# main_board.net
KiCad netlist of a schematic drawn in EAGLE
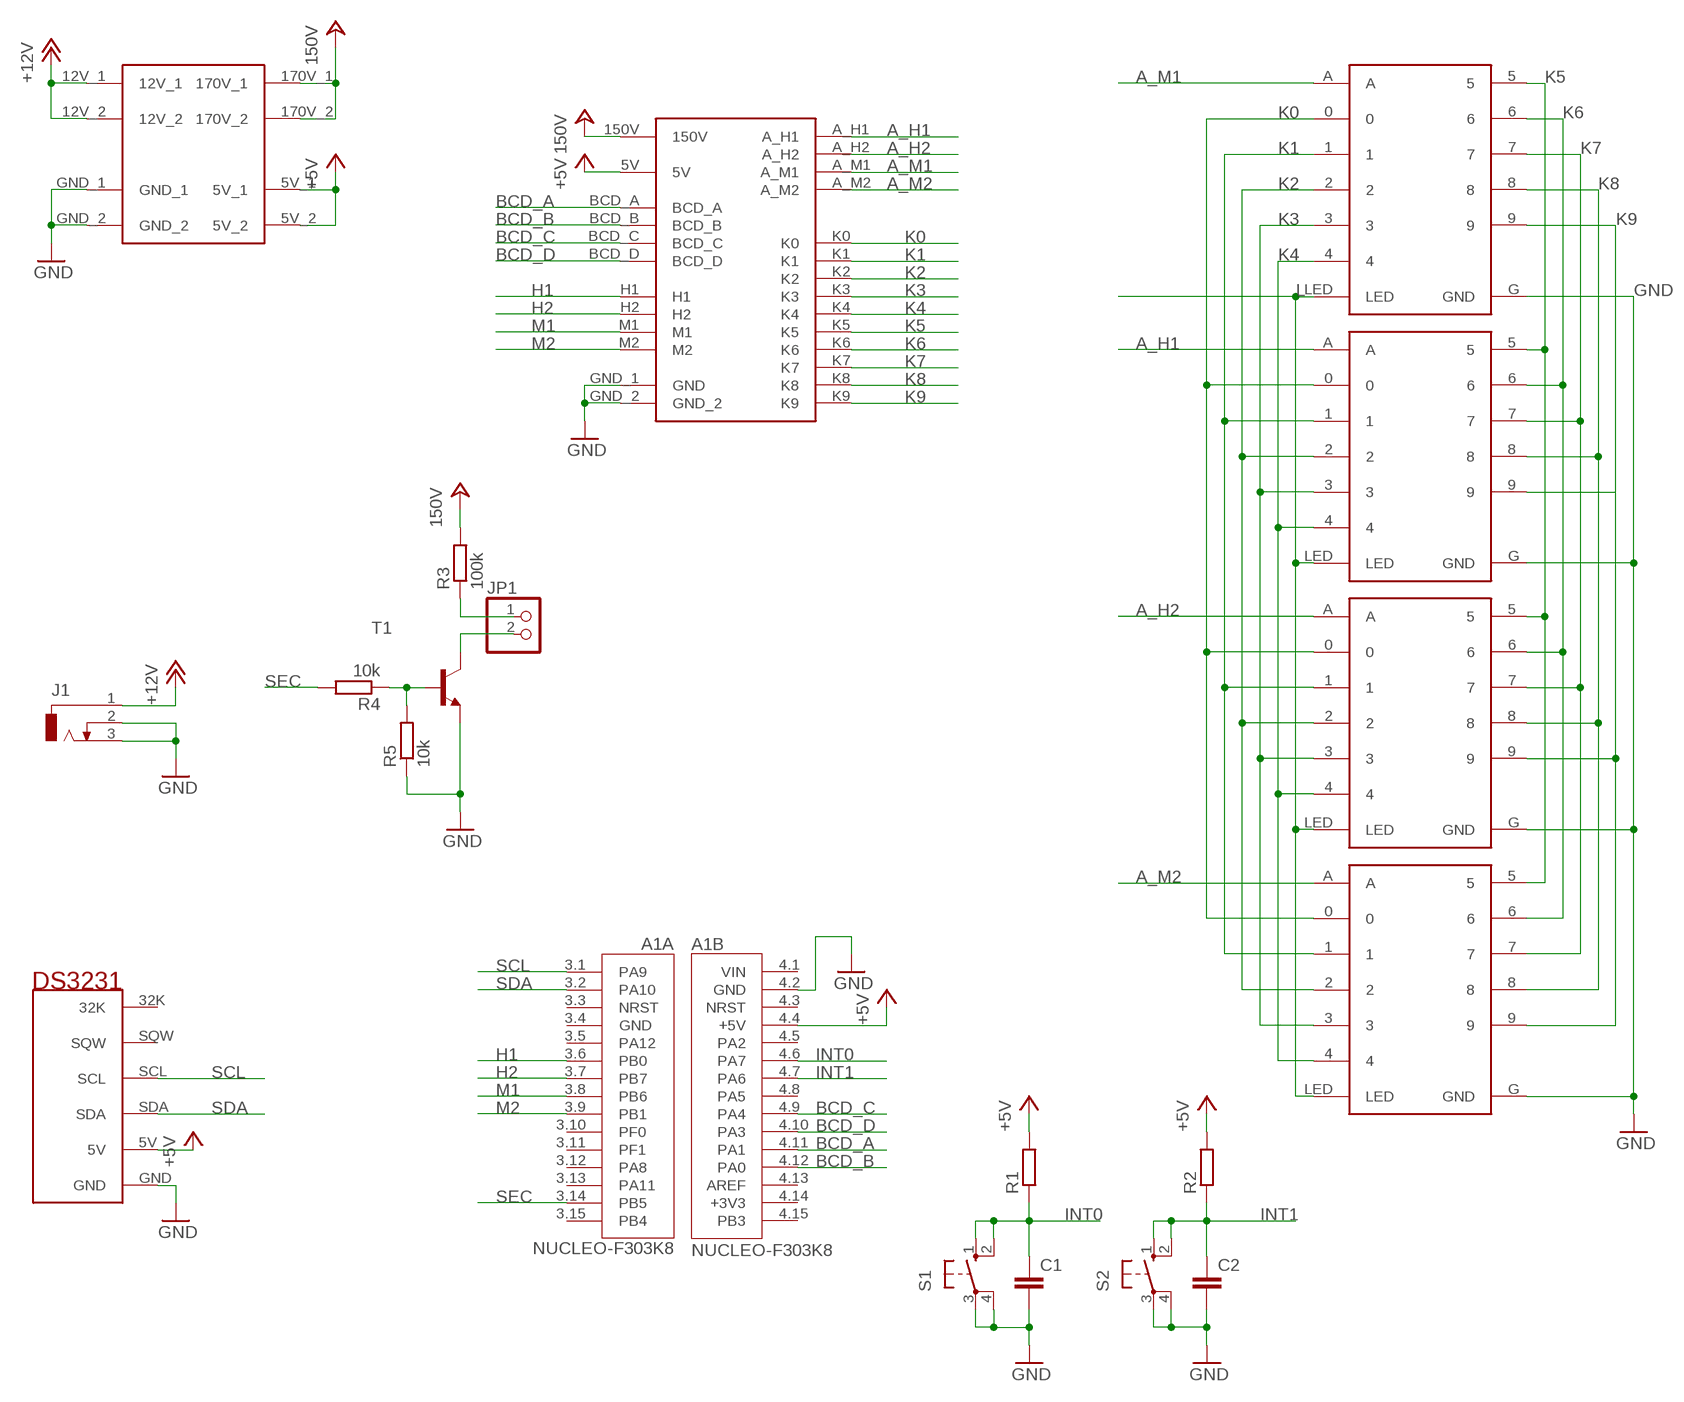
[diagram p0: schematic, sheet 1]

(export (version "E")
  (design (tool "Eeschema 10.0.6"))
  (components
    (comp (ref "A1")
      (value "NUCLEO-F303K8")
      (footprint "eagle-import:MODULE_NUCLEO-F303K8")
      (fields (field (name "MF") "STMicroelectronics"))
      (libsource (lib "eagle-import") (part "NUCLEO-F303K8"))
    )
    (comp (ref "C1")
      (value "C-EUC1206")
      (footprint "eagle-import:C1206")
      (libsource (lib "eagle-import") (part "C-EUC1206"))
    )
    (comp (ref "C2")
      (value "C-EUC1206")
      (footprint "eagle-import:C1206")
      (libsource (lib "eagle-import") (part "C-EUC1206"))
    )
    (comp (ref "J1")
      (value "DCJ0303")
      (footprint "eagle-import:DCJ0303")
      (libsource (lib "eagle-import") (part "DCJ0303"))
    )
    (comp (ref "JP1")
      (value "PINHD-1X2")
      (footprint "eagle-import:1X02")
      (libsource (lib "eagle-import") (part "PINHD-1X2"))
    )
    (comp (ref "R1")
      (value "R-EU_R1206")
      (footprint "eagle-import:R1206")
      (libsource (lib "eagle-import") (part "R-EU_R1206"))
    )
    (comp (ref "R2")
      (value "R-EU_R1206")
      (footprint "eagle-import:R1206")
      (libsource (lib "eagle-import") (part "R-EU_R1206"))
    )
    (comp (ref "R3")
      (value "100k")
      (footprint "eagle-import:R1206")
      (libsource (lib "eagle-import") (part "R-EU_R1206"))
    )
    (comp (ref "R4")
      (value "10k")
      (footprint "eagle-import:R1206")
      (libsource (lib "eagle-import") (part "R-EU_R1206"))
    )
    (comp (ref "R5")
      (value "10k")
      (footprint "eagle-import:R1206")
      (libsource (lib "eagle-import") (part "R-EU_R1206"))
    )
    (comp (ref "S1")
      (value "10-XX")
      (footprint "eagle-import:B3F-10XX")
      (fields (field (name "MPN") "B3F-1000"))
      (libsource (lib "eagle-import") (part "10-XX"))
    )
    (comp (ref "S2")
      (value "10-XX")
      (footprint "eagle-import:B3F-10XX")
      (fields (field (name "MPN") "B3F-1000"))
      (libsource (lib "eagle-import") (part "10-XX"))
    )
    (comp (ref "T1")
      (value "MMBTA42LT1-NPN-SOT23-BEC")
      (footprint "eagle-import:SOT23-BEC")
      (libsource (lib "eagle-import") (part "-NPN-SOT23-BECMMBTA42LT1"))
    )
    (comp (ref "U$1")
      (value "Z570M_MODULE")
      (footprint "eagle-import:Z570M_MODULE")
      (libsource (lib "eagle-import") (part "Z570M_MODULE"))
    )
    (comp (ref "U$2")
      (value "Z570M_MODULE")
      (footprint "eagle-import:Z570M_MODULE")
      (libsource (lib "eagle-import") (part "Z570M_MODULE"))
    )
    (comp (ref "U$3")
      (value "Z570M_MODULE")
      (footprint "eagle-import:Z570M_MODULE")
      (libsource (lib "eagle-import") (part "Z570M_MODULE"))
    )
    (comp (ref "U$4")
      (value "Z570M_MODULE")
      (footprint "eagle-import:Z570M_MODULE")
      (libsource (lib "eagle-import") (part "Z570M_MODULE"))
    )
    (comp (ref "U$5")
      (value "POWER_MOUDLE")
      (footprint "eagle-import:POWER_MODULE")
      (libsource (lib "eagle-import") (part "POWER_MOUDLE"))
    )
    (comp (ref "U$6")
      (value "RTC_MODULE")
      (footprint "eagle-import:RTC_MODULE")
      (libsource (lib "eagle-import") (part "RTC_MODULE"))
    )
    (comp (ref "U$7")
      (value "MATRIX_MODULE")
      (footprint "eagle-import:MATRIX_MODULE")
      (libsource (lib "eagle-import") (part "MATRIX_MODULE"))
    )
  )
  (nets
    (net (code "1") (name "+5V") (class "Default")
      (node (ref "A1") (pin "4.4") (pinfunction "+5V_4.4") (pintype "bidirectional"))
      (node (ref "R1") (pin "2") (pinfunction "2_2") (pintype "passive"))
      (node (ref "R2") (pin "2") (pinfunction "2_2") (pintype "passive"))
      (node (ref "U$5") (pin "5V_1") (pinfunction "5V_1_5V_1") (pintype "bidirectional"))
      (node (ref "U$5") (pin "5V_2") (pinfunction "5V_2_5V_2") (pintype "bidirectional"))
      (node (ref "U$6") (pin "5V") (pinfunction "5V_5V") (pintype "bidirectional"))
      (node (ref "U$7") (pin "5V") (pinfunction "5V_5V") (pintype "bidirectional"))
    )
    (net (code "2") (name "+12V") (class "Default")
      (node (ref "J1") (pin "1") (pinfunction "1_1") (pintype "passive"))
      (node (ref "U$5") (pin "12V_1") (pinfunction "12V_1_12V_1") (pintype "bidirectional"))
      (node (ref "U$5") (pin "12V_2") (pinfunction "12V_2_12V_2") (pintype "bidirectional"))
    )
    (net (code "3") (name "/A_H1") (class "Default")
      (node (ref "U$4") (pin "A") (pinfunction "A_A") (pintype "bidirectional"))
      (node (ref "U$7") (pin "A_H1") (pinfunction "A_H1_A_H1") (pintype "bidirectional"))
    )
    (net (code "4") (name "/A_H2") (class "Default")
      (node (ref "U$3") (pin "A") (pinfunction "A_A") (pintype "bidirectional"))
      (node (ref "U$7") (pin "A_H2") (pinfunction "A_H2_A_H2") (pintype "bidirectional"))
    )
    (net (code "5") (name "/A_M1") (class "Default")
      (node (ref "U$1") (pin "A") (pinfunction "A_A") (pintype "bidirectional"))
      (node (ref "U$7") (pin "A_M1") (pinfunction "A_M1_A_M1") (pintype "bidirectional"))
    )
    (net (code "6") (name "/A_M2") (class "Default")
      (node (ref "U$2") (pin "A") (pinfunction "A_A") (pintype "bidirectional"))
      (node (ref "U$7") (pin "A_M2") (pinfunction "A_M2_A_M2") (pintype "bidirectional"))
    )
    (net (code "7") (name "/BCD_A") (class "Default")
      (node (ref "A1") (pin "4.11") (pinfunction "PA1_4.11") (pintype "bidirectional"))
      (node (ref "U$7") (pin "BCD_A") (pinfunction "BCD_A_BCD_A") (pintype "bidirectional"))
    )
    (net (code "8") (name "/BCD_B") (class "Default")
      (node (ref "A1") (pin "4.12") (pinfunction "PA0_4.12") (pintype "bidirectional"))
      (node (ref "U$7") (pin "BCD_B") (pinfunction "BCD_B_BCD_B") (pintype "bidirectional"))
    )
    (net (code "9") (name "/BCD_C") (class "Default")
      (node (ref "A1") (pin "4.9") (pinfunction "PA4_4.9") (pintype "bidirectional"))
      (node (ref "U$7") (pin "BCD_C") (pinfunction "BCD_C_BCD_C") (pintype "bidirectional"))
    )
    (net (code "10") (name "/BCD_D") (class "Default")
      (node (ref "A1") (pin "4.10") (pinfunction "PA3_4.10") (pintype "bidirectional"))
      (node (ref "U$7") (pin "BCD_D") (pinfunction "BCD_D_BCD_D") (pintype "bidirectional"))
    )
    (net (code "11") (name "/H1") (class "Default")
      (node (ref "A1") (pin "3.6") (pinfunction "PB0_3.6") (pintype "bidirectional"))
      (node (ref "U$7") (pin "H1") (pinfunction "H1_H1") (pintype "bidirectional"))
    )
    (net (code "12") (name "/H2") (class "Default")
      (node (ref "A1") (pin "3.7") (pinfunction "PB7_3.7") (pintype "bidirectional"))
      (node (ref "U$7") (pin "H2") (pinfunction "H2_H2") (pintype "bidirectional"))
    )
    (net (code "13") (name "/INT0") (class "Default")
      (node (ref "A1") (pin "4.6") (pinfunction "PA7_4.6") (pintype "bidirectional"))
      (node (ref "C1") (pin "1") (pinfunction "1_1") (pintype "passive"))
      (node (ref "R1") (pin "1") (pinfunction "1_1") (pintype "passive"))
      (node (ref "S1") (pin "1") (pinfunction "S_1") (pintype "passive"))
      (node (ref "S1") (pin "2") (pinfunction "S1_2") (pintype "passive"))
    )
    (net (code "14") (name "/INT1") (class "Default")
      (node (ref "A1") (pin "4.7") (pinfunction "PA6_4.7") (pintype "bidirectional"))
      (node (ref "C2") (pin "1") (pinfunction "1_1") (pintype "passive"))
      (node (ref "R2") (pin "1") (pinfunction "1_1") (pintype "passive"))
      (node (ref "S2") (pin "1") (pinfunction "S_1") (pintype "passive"))
      (node (ref "S2") (pin "2") (pinfunction "S1_2") (pintype "passive"))
    )
    (net (code "15") (name "/K0") (class "Default")
      (node (ref "U$1") (pin "0") (pinfunction "0_0") (pintype "bidirectional"))
      (node (ref "U$2") (pin "0") (pinfunction "0_0") (pintype "bidirectional"))
      (node (ref "U$3") (pin "0") (pinfunction "0_0") (pintype "bidirectional"))
      (node (ref "U$4") (pin "0") (pinfunction "0_0") (pintype "bidirectional"))
      (node (ref "U$7") (pin "K0") (pinfunction "K0_K0") (pintype "bidirectional"))
    )
    (net (code "16") (name "/K1") (class "Default")
      (node (ref "U$1") (pin "1") (pinfunction "1_1") (pintype "bidirectional"))
      (node (ref "U$2") (pin "1") (pinfunction "1_1") (pintype "bidirectional"))
      (node (ref "U$3") (pin "1") (pinfunction "1_1") (pintype "bidirectional"))
      (node (ref "U$4") (pin "1") (pinfunction "1_1") (pintype "bidirectional"))
      (node (ref "U$7") (pin "K1") (pinfunction "K1_K1") (pintype "bidirectional"))
    )
    (net (code "17") (name "/K2") (class "Default")
      (node (ref "U$1") (pin "2") (pinfunction "2_2") (pintype "bidirectional"))
      (node (ref "U$2") (pin "2") (pinfunction "2_2") (pintype "bidirectional"))
      (node (ref "U$3") (pin "2") (pinfunction "2_2") (pintype "bidirectional"))
      (node (ref "U$4") (pin "2") (pinfunction "2_2") (pintype "bidirectional"))
      (node (ref "U$7") (pin "K2") (pinfunction "K2_K2") (pintype "bidirectional"))
    )
    (net (code "18") (name "/K3") (class "Default")
      (node (ref "U$1") (pin "3") (pinfunction "3_3") (pintype "bidirectional"))
      (node (ref "U$2") (pin "3") (pinfunction "3_3") (pintype "bidirectional"))
      (node (ref "U$3") (pin "3") (pinfunction "3_3") (pintype "bidirectional"))
      (node (ref "U$4") (pin "3") (pinfunction "3_3") (pintype "bidirectional"))
      (node (ref "U$7") (pin "K3") (pinfunction "K3_K3") (pintype "bidirectional"))
    )
    (net (code "19") (name "/K4") (class "Default")
      (node (ref "U$1") (pin "4") (pinfunction "4_4") (pintype "bidirectional"))
      (node (ref "U$2") (pin "4") (pinfunction "4_4") (pintype "bidirectional"))
      (node (ref "U$3") (pin "4") (pinfunction "4_4") (pintype "bidirectional"))
      (node (ref "U$4") (pin "4") (pinfunction "4_4") (pintype "bidirectional"))
      (node (ref "U$7") (pin "K4") (pinfunction "K4_K4") (pintype "bidirectional"))
    )
    (net (code "20") (name "/K5") (class "Default")
      (node (ref "U$1") (pin "5") (pinfunction "5_5") (pintype "bidirectional"))
      (node (ref "U$2") (pin "5") (pinfunction "5_5") (pintype "bidirectional"))
      (node (ref "U$3") (pin "5") (pinfunction "5_5") (pintype "bidirectional"))
      (node (ref "U$4") (pin "5") (pinfunction "5_5") (pintype "bidirectional"))
      (node (ref "U$7") (pin "K5") (pinfunction "K5_K5") (pintype "bidirectional"))
    )
    (net (code "21") (name "/K6") (class "Default")
      (node (ref "U$1") (pin "6") (pinfunction "6_6") (pintype "bidirectional"))
      (node (ref "U$2") (pin "6") (pinfunction "6_6") (pintype "bidirectional"))
      (node (ref "U$3") (pin "6") (pinfunction "6_6") (pintype "bidirectional"))
      (node (ref "U$4") (pin "6") (pinfunction "6_6") (pintype "bidirectional"))
      (node (ref "U$7") (pin "K6") (pinfunction "K6_K6") (pintype "bidirectional"))
    )
    (net (code "22") (name "/K7") (class "Default")
      (node (ref "U$1") (pin "7") (pinfunction "7_7") (pintype "bidirectional"))
      (node (ref "U$2") (pin "7") (pinfunction "7_7") (pintype "bidirectional"))
      (node (ref "U$3") (pin "7") (pinfunction "7_7") (pintype "bidirectional"))
      (node (ref "U$4") (pin "7") (pinfunction "7_7") (pintype "bidirectional"))
      (node (ref "U$7") (pin "K7") (pinfunction "K7_K7") (pintype "bidirectional"))
    )
    (net (code "23") (name "/K8") (class "Default")
      (node (ref "U$1") (pin "8") (pinfunction "8_8") (pintype "bidirectional"))
      (node (ref "U$2") (pin "8") (pinfunction "8_8") (pintype "bidirectional"))
      (node (ref "U$3") (pin "8") (pinfunction "8_8") (pintype "bidirectional"))
      (node (ref "U$4") (pin "8") (pinfunction "8_8") (pintype "bidirectional"))
      (node (ref "U$7") (pin "K8") (pinfunction "K8_K8") (pintype "bidirectional"))
    )
    (net (code "24") (name "/K9") (class "Default")
      (node (ref "U$1") (pin "9") (pinfunction "9_9") (pintype "bidirectional"))
      (node (ref "U$2") (pin "9") (pinfunction "9_9") (pintype "bidirectional"))
      (node (ref "U$3") (pin "9") (pinfunction "9_9") (pintype "bidirectional"))
      (node (ref "U$4") (pin "9") (pinfunction "9_9") (pintype "bidirectional"))
      (node (ref "U$7") (pin "K9") (pinfunction "K9_K9") (pintype "bidirectional"))
    )
    (net (code "25") (name "/L") (class "Default")
      (node (ref "U$1") (pin "LED") (pinfunction "LED_LED") (pintype "bidirectional"))
      (node (ref "U$2") (pin "LED") (pinfunction "LED_LED") (pintype "bidirectional"))
      (node (ref "U$3") (pin "LED") (pinfunction "LED_LED") (pintype "bidirectional"))
      (node (ref "U$4") (pin "LED") (pinfunction "LED_LED") (pintype "bidirectional"))
    )
    (net (code "26") (name "/M1") (class "Default")
      (node (ref "A1") (pin "3.8") (pinfunction "PB6_3.8") (pintype "bidirectional"))
      (node (ref "U$7") (pin "M1") (pinfunction "M1_M1") (pintype "bidirectional"))
    )
    (net (code "27") (name "/M2") (class "Default")
      (node (ref "A1") (pin "3.9") (pinfunction "PB1_3.9") (pintype "bidirectional"))
      (node (ref "U$7") (pin "M2") (pinfunction "M2_M2") (pintype "bidirectional"))
    )
    (net (code "28") (name "/SCL") (class "Default")
      (node (ref "A1") (pin "3.1") (pinfunction "PA9_3.1") (pintype "bidirectional"))
      (node (ref "U$6") (pin "SCL") (pinfunction "SCL_SCL") (pintype "bidirectional"))
    )
    (net (code "29") (name "/SDA") (class "Default")
      (node (ref "A1") (pin "3.2") (pinfunction "PA10_3.2") (pintype "bidirectional"))
      (node (ref "U$6") (pin "SDA") (pinfunction "SDA_SDA") (pintype "bidirectional"))
    )
    (net (code "30") (name "/SEC") (class "Default")
      (node (ref "A1") (pin "3.14") (pinfunction "PB5_3.14") (pintype "bidirectional"))
      (node (ref "R4") (pin "2") (pinfunction "2_2") (pintype "passive"))
    )
    (net (code "31") (name "150V") (class "Default")
      (node (ref "R3") (pin "2") (pinfunction "2_2") (pintype "passive"))
      (node (ref "U$5") (pin "170V_1") (pinfunction "170V_1_170V_1") (pintype "bidirectional"))
      (node (ref "U$5") (pin "170V_2") (pinfunction "170V_2_170V_2") (pintype "bidirectional"))
      (node (ref "U$7") (pin "150V") (pinfunction "150V_150V") (pintype "bidirectional"))
    )
    (net (code "32") (name "GND") (class "Default")
      (node (ref "A1") (pin "4.2") (pinfunction "GND_4.2") (pintype "bidirectional"))
      (node (ref "C1") (pin "2") (pinfunction "2_2") (pintype "passive"))
      (node (ref "C2") (pin "2") (pinfunction "2_2") (pintype "passive"))
      (node (ref "J1") (pin "2") (pinfunction "2_2") (pintype "passive"))
      (node (ref "J1") (pin "3") (pinfunction "3_3") (pintype "passive"))
      (node (ref "R5") (pin "1") (pinfunction "1_1") (pintype "passive"))
      (node (ref "S1") (pin "3") (pinfunction "P_3") (pintype "passive"))
      (node (ref "S1") (pin "4") (pinfunction "P1_4") (pintype "passive"))
      (node (ref "S2") (pin "3") (pinfunction "P_3") (pintype "passive"))
      (node (ref "S2") (pin "4") (pinfunction "P1_4") (pintype "passive"))
      (node (ref "T1") (pin "E") (pinfunction "E_E") (pintype "passive"))
      (node (ref "U$1") (pin "G") (pinfunction "GND_G") (pintype "bidirectional"))
      (node (ref "U$2") (pin "G") (pinfunction "GND_G") (pintype "bidirectional"))
      (node (ref "U$3") (pin "G") (pinfunction "GND_G") (pintype "bidirectional"))
      (node (ref "U$4") (pin "G") (pinfunction "GND_G") (pintype "bidirectional"))
      (node (ref "U$5") (pin "GND_1") (pinfunction "GND_1_GND_1") (pintype "bidirectional"))
      (node (ref "U$5") (pin "GND_2") (pinfunction "GND_2_GND_2") (pintype "bidirectional"))
      (node (ref "U$6") (pin "GND") (pinfunction "GND_GND") (pintype "bidirectional"))
      (node (ref "U$7") (pin "GND_1") (pinfunction "GND_GND_1") (pintype "bidirectional"))
      (node (ref "U$7") (pin "GND_2") (pinfunction "GND_2_GND_2") (pintype "bidirectional"))
    )
    (net (code "33") (name "Net-(JP1-Pad1)") (class "Default")
      (node (ref "JP1") (pin "1") (pinfunction "1_1") (pintype "passive"))
      (node (ref "R3") (pin "1") (pinfunction "1_1") (pintype "passive"))
    )
    (net (code "34") (name "Net-(JP1-Pad2)") (class "Default")
      (node (ref "JP1") (pin "2") (pinfunction "2_2") (pintype "passive"))
      (node (ref "T1") (pin "C") (pinfunction "C_C") (pintype "passive"))
    )
    (net (code "35") (name "Net-(R4-Pad1)") (class "Default")
      (node (ref "R4") (pin "1") (pinfunction "1_1") (pintype "passive"))
      (node (ref "R5") (pin "2") (pinfunction "2_2") (pintype "passive"))
      (node (ref "T1") (pin "B") (pinfunction "B_B") (pintype "passive"))
    )
    (net (code "36") (name "unconnected-(A1A-GND-Pad3.4)") (class "Default")
      (node (ref "A1") (pin "3.4") (pinfunction "GND_3.4") (pintype "bidirectional"))
    )
    (net (code "37") (name "unconnected-(A1A-NRST-Pad3.3)") (class "Default")
      (node (ref "A1") (pin "3.3") (pinfunction "NRST_3.3") (pintype "bidirectional"))
    )
    (net (code "38") (name "unconnected-(A1A-PA8-Pad3.12)") (class "Default")
      (node (ref "A1") (pin "3.12") (pinfunction "PA8_3.12") (pintype "bidirectional"))
    )
    (net (code "39") (name "unconnected-(A1A-PA11-Pad3.13)") (class "Default")
      (node (ref "A1") (pin "3.13") (pinfunction "PA11_3.13") (pintype "bidirectional"))
    )
    (net (code "40") (name "unconnected-(A1A-PA12-Pad3.5)") (class "Default")
      (node (ref "A1") (pin "3.5") (pinfunction "PA12_3.5") (pintype "bidirectional"))
    )
    (net (code "41") (name "unconnected-(A1A-PB4-Pad3.15)") (class "Default")
      (node (ref "A1") (pin "3.15") (pinfunction "PB4_3.15") (pintype "bidirectional"))
    )
    (net (code "42") (name "unconnected-(A1A-PF0-Pad3.10)") (class "Default")
      (node (ref "A1") (pin "3.10") (pinfunction "PF0_3.10") (pintype "bidirectional"))
    )
    (net (code "43") (name "unconnected-(A1A-PF1-Pad3.11)") (class "Default")
      (node (ref "A1") (pin "3.11") (pinfunction "PF1_3.11") (pintype "bidirectional"))
    )
    (net (code "44") (name "unconnected-(A1B-+3V3-Pad4.14)") (class "Default")
      (node (ref "A1") (pin "4.14") (pinfunction "+3V3_4.14") (pintype "bidirectional"))
    )
    (net (code "45") (name "unconnected-(A1B-AREF-Pad4.13)") (class "Default")
      (node (ref "A1") (pin "4.13") (pinfunction "AREF_4.13") (pintype "bidirectional"))
    )
    (net (code "46") (name "unconnected-(A1B-NRST-Pad4.3)") (class "Default")
      (node (ref "A1") (pin "4.3") (pinfunction "NRST_4.3") (pintype "bidirectional"))
    )
    (net (code "47") (name "unconnected-(A1B-PA2-Pad4.5)") (class "Default")
      (node (ref "A1") (pin "4.5") (pinfunction "PA2_4.5") (pintype "bidirectional"))
    )
    (net (code "48") (name "unconnected-(A1B-PA5-Pad4.8)") (class "Default")
      (node (ref "A1") (pin "4.8") (pinfunction "PA5_4.8") (pintype "bidirectional"))
    )
    (net (code "49") (name "unconnected-(A1B-PB3-Pad4.15)") (class "Default")
      (node (ref "A1") (pin "4.15") (pinfunction "PB3_4.15") (pintype "bidirectional"))
    )
    (net (code "50") (name "unconnected-(A1B-VIN-Pad4.1)") (class "Default")
      (node (ref "A1") (pin "4.1") (pinfunction "VIN_4.1") (pintype "bidirectional"))
    )
    (net (code "51") (name "unconnected-(U$6-Pad32K)") (class "Default")
      (node (ref "U$6") (pin "32K") (pinfunction "32K_32K") (pintype "bidirectional"))
    )
    (net (code "52") (name "unconnected-(U$6-PadSQW)") (class "Default")
      (node (ref "U$6") (pin "SQW") (pinfunction "SQW_SQW") (pintype "bidirectional"))
    )
  )
)
